# bluetooth.net
KiCad netlist of a schematic drawn in Altium Designer
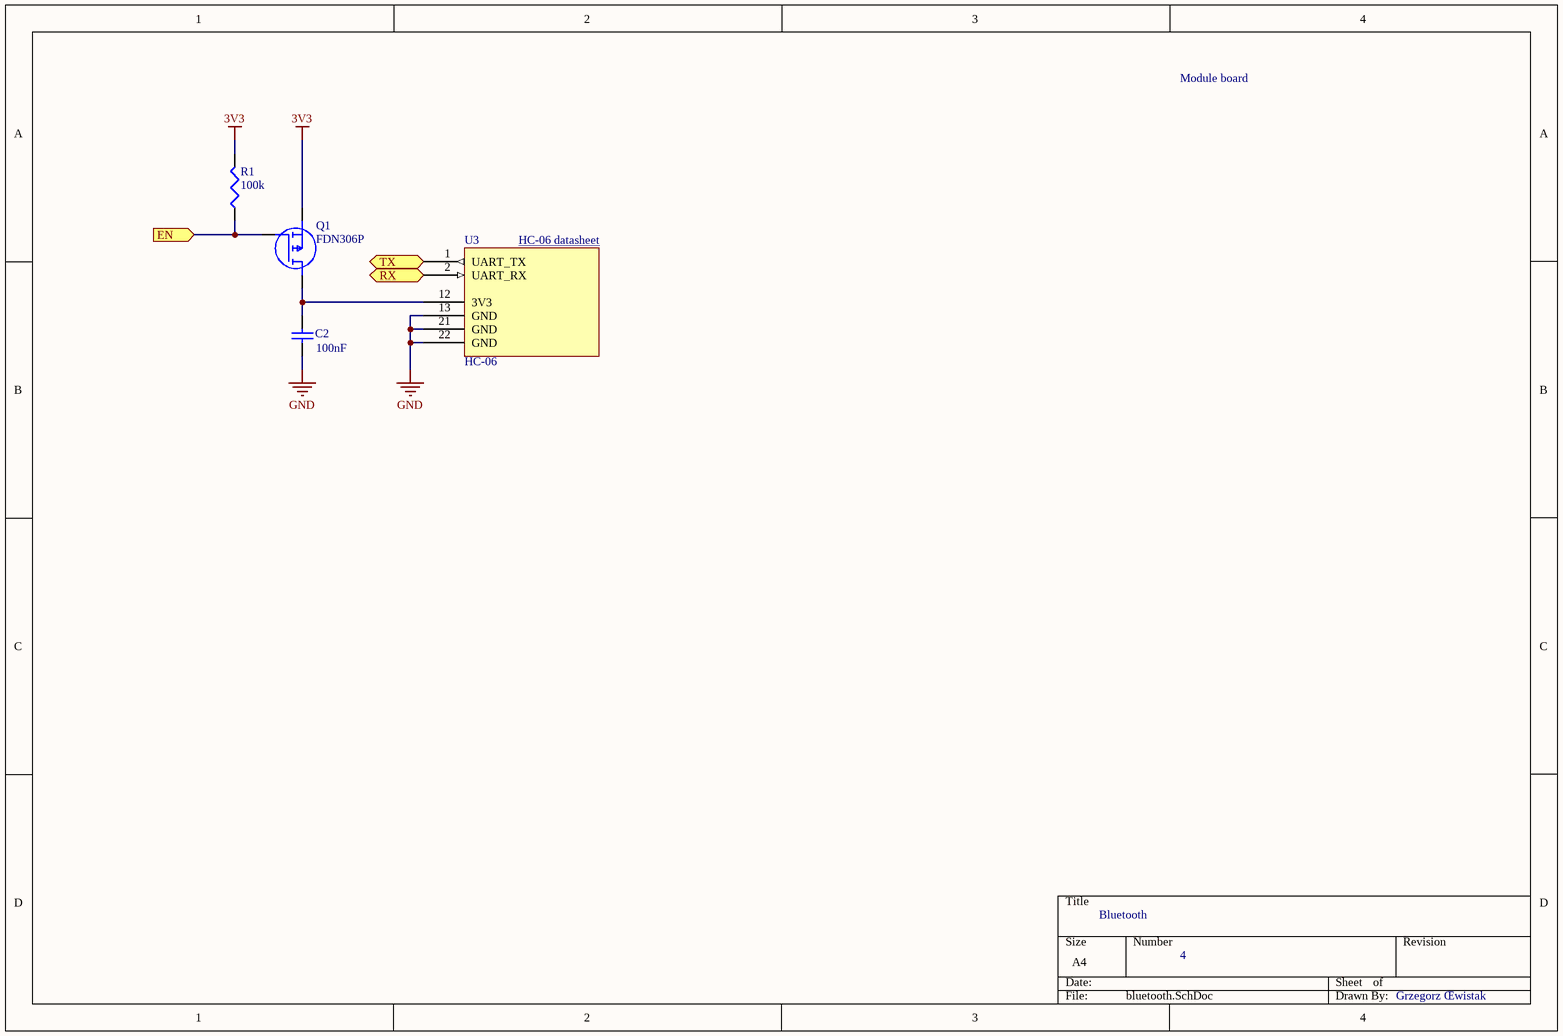
[diagram p0: bluetooth.SchDoc]

(export (version "E")
  (design (tool "Eeschema 10.0.6"))
  (components
    (comp (ref "C2")
      (value "100nF")
      (footprint "C0805")
      (description "Capacitor")
      (fields (field (name "Comment") "Cap") (field (name "PUBLISHER") "Altium Limited"))
      (libsource (lib "Miscellaneous Devices") (part "Cap"))
    )
    (comp (ref "Q1")
      (value "FDN306P")
      (footprint "SOT95P237X112-3N")
      (description "MOSFET (P-Channel)")
      (fields (field (name "MOUSER PART NUMBER") "512-FDN306P"))
      (libsource (lib "lib") (part "FDN306P"))
    )
    (comp (ref "R1")
      (value "100k")
      (footprint "R0603")
      (description "Resistor")
      (fields (field (name "Comment") "Res3") (field (name "PUBLISHER") "Altium Limited"))
      (libsource (lib "Miscellaneous Devices") (part "Res3"))
    )
    (comp (ref "U3")
      (value "HC-06")
      (footprint "HC-06_footprint_minimal_pin_number")
      (description "HC-06 bluetooth module")
      (libsource (lib "lib") (part "HC-06"))
    )
  )
  (nets
    (net (code "1") (name "/EN") (class "Default")
      (node (ref "Q1") (pin "1") (pinfunction "G_1") (pintype "passive"))
      (node (ref "R1") (pin "1") (pinfunction "1_1") (pintype "passive"))
    )
    (net (code "2") (name "/RX") (class "Default")
      (node (ref "U3") (pin "2") (pinfunction "UART_RX_2") (pintype "input"))
    )
    (net (code "3") (name "/TX") (class "Default")
      (node (ref "U3") (pin "1") (pinfunction "UART_TX_1") (pintype "output"))
    )
    (net (code "4") (name "3V3") (class "Default")
      (node (ref "Q1") (pin "2") (pinfunction "S_2") (pintype "passive"))
      (node (ref "R1") (pin "2") (pinfunction "2_2") (pintype "passive"))
    )
    (net (code "5") (name "GND") (class "Default")
      (node (ref "C2") (pin "1") (pinfunction "1_1") (pintype "passive"))
      (node (ref "U3") (pin "13") (pinfunction "GND_13") (pintype "passive"))
      (node (ref "U3") (pin "21") (pinfunction "GND_21") (pintype "passive"))
      (node (ref "U3") (pin "22") (pinfunction "GND_22") (pintype "passive"))
    )
    (net (code "6") (name "Net-(Q1-D)") (class "Default")
      (node (ref "C2") (pin "2") (pinfunction "2_2") (pintype "passive"))
      (node (ref "Q1") (pin "3") (pinfunction "D_3") (pintype "passive"))
      (node (ref "U3") (pin "12") (pinfunction "3V3_12") (pintype "passive"))
    )
  )
)
